# Ammeter_Design.net
KiCad netlist of a schematic drawn in Altium Designer
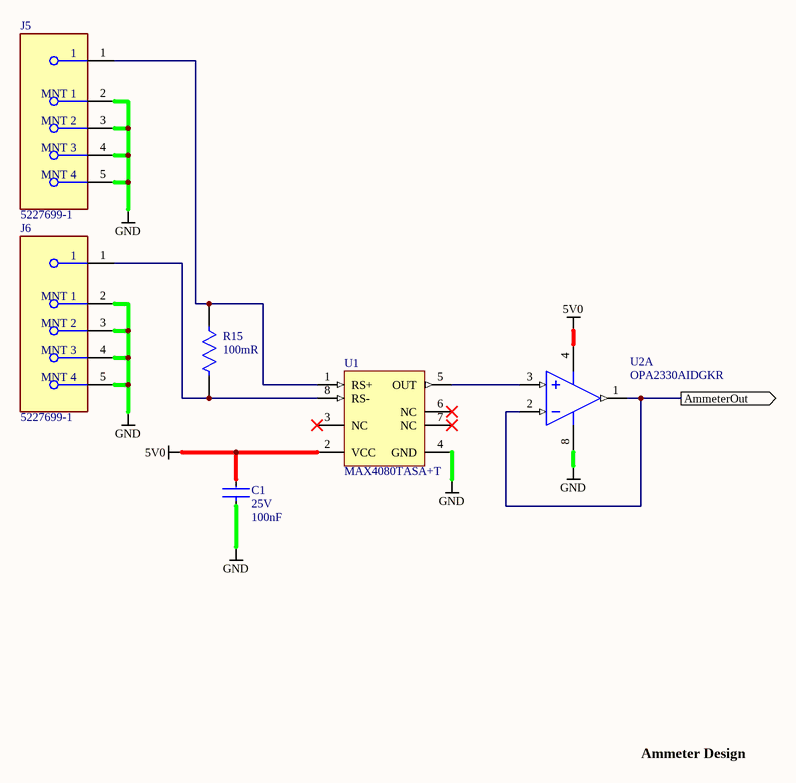
[diagram p0: Ammeter Design.SchDoc]

(export (version "E")
  (design (tool "Eeschema 10.0.6"))
  (components
    (comp (ref "C1")
      (value "0.1 uF_CL05A104KA5NNNC")
      (footprint "FP-CL278-IPC_C")
      (description "Cap Ceramic 100nF 25V X5R ±10% SMD 0402 +85°C Paper T/R")
      (fields
        (field (name "VOLTAGE") "25V")
        (field (name "TOLERANCE") "10%")
        (field (name "CAPACITANCE") "100nF")
      )
      (libsource (lib "Altium Content Vault") (part "b4654b650e69147ec39a6b967a45e02"))
    )
    (comp (ref "J5")
      (value "5227699-1")
      (footprint "FP-5227699-1-MFG")
      (description "CONN BNC JACK STR 50 OHM PCB")
      (libsource (lib "Altium Content Vault") (part "c65b8a639cdaef1819ea20b5466f8fa"))
    )
    (comp (ref "J6")
      (value "5227699-1")
      (footprint "FP-5227699-1-MFG")
      (description "CONN BNC JACK STR 50 OHM PCB")
      (libsource (lib "Altium Content Vault") (part "c65b8a639cdaef1819ea20b5466f8fa"))
    )
    (comp (ref "R15")
      (value "0.1 Ohm")
      (footprint "FP-CSR1206-IPC_B")
      (description "General Purpose Thick Film Chip Resistor, 1206, 0.1Ω, 1%, 100ppm/°C, 0.5W")
      (fields (field (name "TOLERANCE") "1%") (field (name "RESISTANCE") "100mR"))
      (libsource (lib "Altium Content Vault") (part "1029c3af85768c4190bb7ad29bc67b5"))
    )
    (comp (ref "U1")
      (value "MAX4080TASA+T")
      (footprint "MAXM-S8+2_M")
      (libsource (lib "Altium Content Vault") (part "MAX4080-X8_1_2"))
    )
    (comp (ref "U2")
      (value "OPA2330AIDGKR")
      (footprint "DGK0008A_M")
      (fields (field (name "MANUFACTURER") "Texas Instruments"))
      (libsource (lib "Altium Content Vault") (part "TI-OPA-8_2"))
    )
  )
  (nets
    (net (code "1") (name "/AmmeterOut") (class "Default")
      (node (ref "U2") (pin "1") (pinfunction "OUT_A_1") (pintype "output"))
      (node (ref "U2") (pin "2") (pinfunction "IN_A-_2") (pintype "input"))
    )
    (net (code "2") (name "5V0") (class "Default")
      (node (ref "C1") (pin "2") (pinfunction "2_2") (pintype "passive"))
      (node (ref "U1") (pin "2") (pinfunction "VCC_2") (pintype "power_in"))
      (node (ref "U2") (pin "4") (pinfunction "V-_4") (pintype "power_in"))
    )
    (net (code "3") (name "GND") (class "Default")
      (node (ref "C1") (pin "1") (pinfunction "1_1") (pintype "passive"))
      (node (ref "J5") (pin "2") (pinfunction "MNT_1_2") (pintype "passive"))
      (node (ref "J5") (pin "3") (pinfunction "MNT_2_3") (pintype "passive"))
      (node (ref "J5") (pin "4") (pinfunction "MNT_3_4") (pintype "passive"))
      (node (ref "J5") (pin "5") (pinfunction "MNT_4_5") (pintype "passive"))
      (node (ref "J6") (pin "2") (pinfunction "MNT_1_2") (pintype "passive"))
      (node (ref "J6") (pin "3") (pinfunction "MNT_2_3") (pintype "passive"))
      (node (ref "J6") (pin "4") (pinfunction "MNT_3_4") (pintype "passive"))
      (node (ref "J6") (pin "5") (pinfunction "MNT_4_5") (pintype "passive"))
      (node (ref "U1") (pin "4") (pinfunction "GND_4") (pintype "power_in"))
      (node (ref "U2") (pin "8") (pinfunction "V+_8") (pintype "power_in"))
    )
    (net (code "4") (name "Net-(U1-OUT)") (class "Default")
      (node (ref "U1") (pin "5") (pinfunction "OUT_5") (pintype "output"))
      (node (ref "U2") (pin "3") (pinfunction "IN_A+_3") (pintype "input"))
    )
    (net (code "5") (name "Net-(U1-RS+)") (class "Default")
      (node (ref "J5") (pin "1") (pinfunction "1_1") (pintype "passive"))
      (node (ref "R15") (pin "1") (pinfunction "1_1") (pintype "passive"))
      (node (ref "U1") (pin "1") (pinfunction "RS+_1") (pintype "input"))
    )
    (net (code "6") (name "Net-(U1-RS-)") (class "Default")
      (node (ref "J6") (pin "1") (pinfunction "1_1") (pintype "passive"))
      (node (ref "R15") (pin "2") (pinfunction "2_2") (pintype "passive"))
      (node (ref "U1") (pin "8") (pinfunction "RS-_8") (pintype "input"))
    )
    (net (code "7") (name "unconnected-(U1-NC-Pad3)") (class "Default")
      (node (ref "U1") (pin "3") (pinfunction "NC_3") (pintype "passive+no_connect"))
    )
    (net (code "8") (name "unconnected-(U1-NC-Pad6)") (class "Default")
      (node (ref "U1") (pin "6") (pinfunction "NC_6") (pintype "passive+no_connect"))
    )
    (net (code "9") (name "unconnected-(U1-NC-Pad7)") (class "Default")
      (node (ref "U1") (pin "7") (pinfunction "NC_7") (pintype "passive+no_connect"))
    )
  )
)
